# ball_presence_led.net
KiCad netlist of a schematic drawn in EAGLE
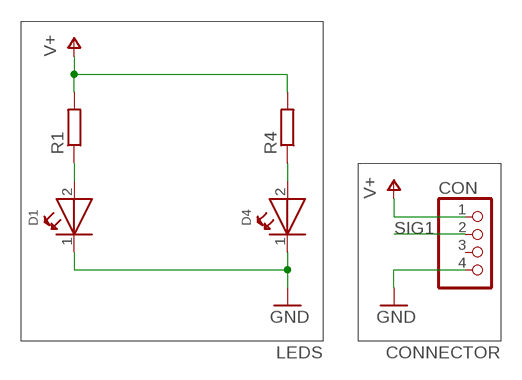
[diagram p0: schematic, sheet 1]

(export (version "E")
  (design (tool "Eeschema 10.0.6"))
  (components
    (comp (ref "CON")
      (value "PINHD-1X4")
      (footprint "eagle-import:1X04")
      (libsource (lib "eagle-import") (part "PINHD-1X4"))
    )
    (comp (ref "D1")
      (value "WL-SMTW-150141AS73100-A")
      (footprint "eagle-import:3528-2PIN")
      (fields
        (field (name "MANUFACTURER") "Würth Elektronik eiSos GmbH")
        (field (name "CREATED-BY") "Christin Otto")
      )
      (libsource (lib "eagle-import") (part "WL-SMTW-150141AS73100-A"))
    )
    (comp (ref "D4")
      (value "WL-SMTW-150141AS73100-A")
      (footprint "eagle-import:3528-2PIN")
      (fields
        (field (name "MANUFACTURER") "Würth Elektronik eiSos GmbH")
        (field (name "CREATED-BY") "Christin Otto")
      )
      (libsource (lib "eagle-import") (part "WL-SMTW-150141AS73100-A"))
    )
    (comp (ref "R1")
      (value "R-EU_R0805")
      (footprint "eagle-import:R0805")
      (libsource (lib "eagle-import") (part "R-EU_R0805"))
    )
    (comp (ref "R4")
      (value "R-EU_R0805")
      (footprint "eagle-import:R0805")
      (libsource (lib "eagle-import") (part "R-EU_R0805"))
    )
  )
  (nets
    (net (code "1") (name "/SIG1") (class "Default")
      (node (ref "CON") (pin "2") (pinfunction "2_2") (pintype "passive"))
    )
    (net (code "2") (name "GND") (class "Default")
      (node (ref "CON") (pin "4") (pinfunction "4_4") (pintype "passive"))
      (node (ref "D1") (pin "1") (pinfunction "K_1") (pintype "bidirectional"))
      (node (ref "D4") (pin "1") (pinfunction "K_1") (pintype "bidirectional"))
    )
    (net (code "3") (name "Net-(D1-A)") (class "Default")
      (node (ref "D1") (pin "2") (pinfunction "A_2") (pintype "bidirectional"))
      (node (ref "R1") (pin "1") (pinfunction "1_1") (pintype "passive"))
    )
    (net (code "4") (name "Net-(D4-A)") (class "Default")
      (node (ref "D4") (pin "2") (pinfunction "A_2") (pintype "bidirectional"))
      (node (ref "R4") (pin "1") (pinfunction "1_1") (pintype "passive"))
    )
    (net (code "5") (name "V+") (class "Default")
      (node (ref "CON") (pin "1") (pinfunction "1_1") (pintype "passive"))
      (node (ref "R1") (pin "2") (pinfunction "2_2") (pintype "passive"))
      (node (ref "R4") (pin "2") (pinfunction "2_2") (pintype "passive"))
    )
    (net (code "6") (name "unconnected-(CON-Pad3)") (class "Default")
      (node (ref "CON") (pin "3") (pinfunction "3_3") (pintype "passive"))
    )
  )
)
